# FlashPanelV6_2.net
KiCad netlist of a schematic drawn in EAGLE
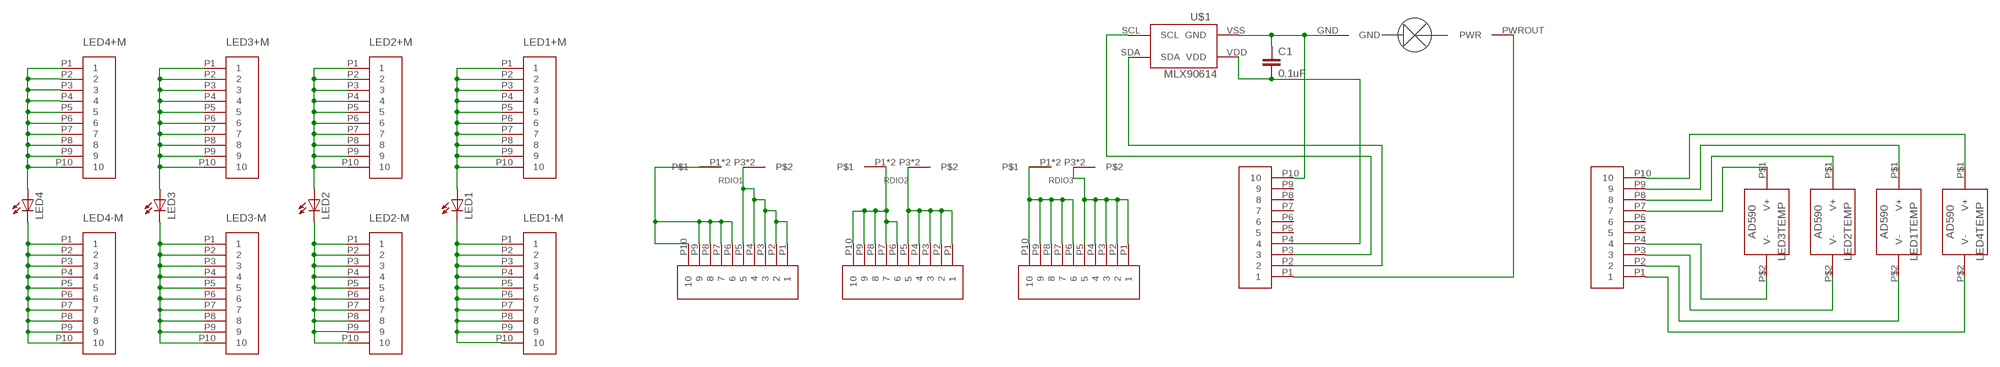
[diagram p0: schematic, sheet 1]

(export (version "E")
  (design (tool "Eeschema 10.0.6"))
  (components
    (comp (ref "ANTDEP1M")
      (value "10PINMALE")
      (footprint "eagle-import:10PINMALE")
      (libsource (lib "eagle-import") (part "cxm27_10PINMALE"))
    )
    (comp (ref "ANTDEP2M")
      (value "10PINMALE")
      (footprint "eagle-import:10PINMALE")
      (libsource (lib "eagle-import") (part "cxm27_10PINMALE"))
    )
    (comp (ref "ANTDEP3M")
      (value "10PINMALE")
      (footprint "eagle-import:10PINMALE")
      (libsource (lib "eagle-import") (part "cxm27_10PINMALE"))
    )
    (comp (ref "C1")
      (value "0.1uF")
      (footprint "eagle-import:0805")
      (libsource (lib "eagle-import") (part "CAP0805"))
    )
    (comp (ref "CONN13M")
      (value "10PINMALE")
      (footprint "eagle-import:10PINMALE")
      (libsource (lib "eagle-import") (part "cxm27_10PINMALE"))
    )
    (comp (ref "LED1")
      (value "CXM27")
      (footprint "eagle-import:CXM27")
      (libsource (lib "eagle-import") (part "CXM27"))
    )
    (comp (ref "LED1+M")
      (value "10PINMALE")
      (footprint "eagle-import:10PINMALE")
      (libsource (lib "eagle-import") (part "10PINMALE"))
    )
    (comp (ref "LED1-M")
      (value "10PINMALE")
      (footprint "eagle-import:10PINMALE")
      (libsource (lib "eagle-import") (part "10PINMALE"))
    )
    (comp (ref "LED1TEMP")
      (value "AD590-TH")
      (footprint "eagle-import:AD590TH")
      (libsource (lib "eagle-import") (part "AD590-TH"))
    )
    (comp (ref "LED2")
      (value "CXM27")
      (footprint "eagle-import:CXM27")
      (libsource (lib "eagle-import") (part "CXM27"))
    )
    (comp (ref "LED2+M")
      (value "10PINMALE")
      (footprint "eagle-import:10PINMALE")
      (libsource (lib "eagle-import") (part "10PINMALE"))
    )
    (comp (ref "LED2-M")
      (value "10PINMALE")
      (footprint "eagle-import:10PINMALE")
      (libsource (lib "eagle-import") (part "10PINMALE"))
    )
    (comp (ref "LED2TEMP")
      (value "AD590-TH")
      (footprint "eagle-import:AD590TH")
      (libsource (lib "eagle-import") (part "AD590-TH"))
    )
    (comp (ref "LED3")
      (value "CXM27")
      (footprint "eagle-import:CXM27")
      (libsource (lib "eagle-import") (part "CXM27"))
    )
    (comp (ref "LED3+M")
      (value "10PINMALE")
      (footprint "eagle-import:10PINMALE")
      (libsource (lib "eagle-import") (part "10PINMALE"))
    )
    (comp (ref "LED3-M")
      (value "10PINMALE")
      (footprint "eagle-import:10PINMALE")
      (libsource (lib "eagle-import") (part "10PINMALE"))
    )
    (comp (ref "LED3TEMP")
      (value "AD590-TH")
      (footprint "eagle-import:AD590TH")
      (libsource (lib "eagle-import") (part "AD590-TH"))
    )
    (comp (ref "LED4")
      (value "CXM27")
      (footprint "eagle-import:CXM27")
      (libsource (lib "eagle-import") (part "CXM27"))
    )
    (comp (ref "LED4+M")
      (value "10PINMALE")
      (footprint "eagle-import:10PINMALE")
      (libsource (lib "eagle-import") (part "10PINMALE"))
    )
    (comp (ref "LED4-M")
      (value "10PINMALE")
      (footprint "eagle-import:10PINMALE")
      (libsource (lib "eagle-import") (part "10PINMALE"))
    )
    (comp (ref "LED4TEMP")
      (value "AD590-TH")
      (footprint "eagle-import:AD590TH")
      (libsource (lib "eagle-import") (part "AD590-TH"))
    )
    (comp (ref "RDIO1")
      (value "RDIO")
      (footprint "eagle-import:RDIO_DPLY")
      (libsource (lib "eagle-import") (part "RDIO"))
    )
    (comp (ref "RDIO2")
      (value "RDIO")
      (footprint "eagle-import:RDIO_DPLY")
      (libsource (lib "eagle-import") (part "RDIO"))
    )
    (comp (ref "RDIO3")
      (value "RDIO")
      (footprint "eagle-import:RDIO_DPLY")
      (libsource (lib "eagle-import") (part "RDIO"))
    )
    (comp (ref "TEMPCONNM")
      (value "10PINMALE")
      (footprint "eagle-import:10PINMALE")
      (libsource (lib "eagle-import") (part "cxm27_10PINMALE"))
    )
    (comp (ref "U$1")
      (value "MXL90614")
      (footprint "eagle-import:MXL90620")
      (libsource (lib "eagle-import") (part "MXL90614"))
    )
    (comp (ref "U$2")
      (value "PHOTODETECTBOTTOM")
      (footprint "eagle-import:PHOTODETECTBOTTOM")
      (libsource (lib "eagle-import") (part "PHOTODETECTBOTTOM"))
    )
  )
  (nets
    (net (code "1") (name "Net-(ANTDEP1M-1)") (class "Default")
      (node (ref "ANTDEP1M") (pin "P1") (pinfunction "1_P1") (pintype "bidirectional"))
      (node (ref "ANTDEP1M") (pin "P2") (pinfunction "2_P2") (pintype "bidirectional"))
      (node (ref "ANTDEP1M") (pin "P3") (pinfunction "3_P3") (pintype "bidirectional"))
      (node (ref "ANTDEP1M") (pin "P4") (pinfunction "4_P4") (pintype "bidirectional"))
      (node (ref "ANTDEP1M") (pin "P5") (pinfunction "5_P5") (pintype "bidirectional"))
      (node (ref "RDIO1") (pin "P3") (pinfunction "P$2_P3") (pintype "bidirectional"))
      (node (ref "RDIO1") (pin "P4") (pinfunction "P$2_P4") (pintype "bidirectional"))
    )
    (net (code "2") (name "Net-(ANTDEP1M-10)") (class "Default")
      (node (ref "ANTDEP1M") (pin "P10") (pinfunction "10_P10") (pintype "bidirectional"))
      (node (ref "ANTDEP1M") (pin "P6") (pinfunction "6_P6") (pintype "bidirectional"))
      (node (ref "ANTDEP1M") (pin "P7") (pinfunction "7_P7") (pintype "bidirectional"))
      (node (ref "ANTDEP1M") (pin "P8") (pinfunction "8_P8") (pintype "bidirectional"))
      (node (ref "ANTDEP1M") (pin "P9") (pinfunction "9_P9") (pintype "bidirectional"))
      (node (ref "RDIO1") (pin "P1") (pinfunction "P$1_P1") (pintype "bidirectional"))
      (node (ref "RDIO1") (pin "P2") (pinfunction "P$1_P2") (pintype "bidirectional"))
    )
    (net (code "3") (name "Net-(ANTDEP2M-1)") (class "Default")
      (node (ref "ANTDEP2M") (pin "P1") (pinfunction "1_P1") (pintype "bidirectional"))
      (node (ref "ANTDEP2M") (pin "P2") (pinfunction "2_P2") (pintype "bidirectional"))
      (node (ref "ANTDEP2M") (pin "P3") (pinfunction "3_P3") (pintype "bidirectional"))
      (node (ref "ANTDEP2M") (pin "P4") (pinfunction "4_P4") (pintype "bidirectional"))
      (node (ref "ANTDEP2M") (pin "P5") (pinfunction "5_P5") (pintype "bidirectional"))
      (node (ref "RDIO2") (pin "P3") (pinfunction "P$2_P3") (pintype "bidirectional"))
      (node (ref "RDIO2") (pin "P4") (pinfunction "P$2_P4") (pintype "bidirectional"))
    )
    (net (code "4") (name "Net-(ANTDEP2M-10)") (class "Default")
      (node (ref "ANTDEP2M") (pin "P10") (pinfunction "10_P10") (pintype "bidirectional"))
      (node (ref "ANTDEP2M") (pin "P6") (pinfunction "6_P6") (pintype "bidirectional"))
      (node (ref "ANTDEP2M") (pin "P7") (pinfunction "7_P7") (pintype "bidirectional"))
      (node (ref "ANTDEP2M") (pin "P8") (pinfunction "8_P8") (pintype "bidirectional"))
      (node (ref "ANTDEP2M") (pin "P9") (pinfunction "9_P9") (pintype "bidirectional"))
      (node (ref "RDIO2") (pin "P1") (pinfunction "P$1_P1") (pintype "bidirectional"))
      (node (ref "RDIO2") (pin "P2") (pinfunction "P$1_P2") (pintype "bidirectional"))
    )
    (net (code "5") (name "Net-(ANTDEP3M-1)") (class "Default")
      (node (ref "ANTDEP3M") (pin "P1") (pinfunction "1_P1") (pintype "bidirectional"))
      (node (ref "ANTDEP3M") (pin "P2") (pinfunction "2_P2") (pintype "bidirectional"))
      (node (ref "ANTDEP3M") (pin "P3") (pinfunction "3_P3") (pintype "bidirectional"))
      (node (ref "ANTDEP3M") (pin "P4") (pinfunction "4_P4") (pintype "bidirectional"))
      (node (ref "ANTDEP3M") (pin "P5") (pinfunction "5_P5") (pintype "bidirectional"))
      (node (ref "RDIO3") (pin "P3") (pinfunction "P$2_P3") (pintype "bidirectional"))
      (node (ref "RDIO3") (pin "P4") (pinfunction "P$2_P4") (pintype "bidirectional"))
    )
    (net (code "6") (name "Net-(ANTDEP3M-10)") (class "Default")
      (node (ref "ANTDEP3M") (pin "P10") (pinfunction "10_P10") (pintype "bidirectional"))
      (node (ref "ANTDEP3M") (pin "P6") (pinfunction "6_P6") (pintype "bidirectional"))
      (node (ref "ANTDEP3M") (pin "P7") (pinfunction "7_P7") (pintype "bidirectional"))
      (node (ref "ANTDEP3M") (pin "P8") (pinfunction "8_P8") (pintype "bidirectional"))
      (node (ref "ANTDEP3M") (pin "P9") (pinfunction "9_P9") (pintype "bidirectional"))
      (node (ref "RDIO3") (pin "P1") (pinfunction "P$1_P1") (pintype "bidirectional"))
      (node (ref "RDIO3") (pin "P2") (pinfunction "P$1_P2") (pintype "bidirectional"))
    )
    (net (code "7") (name "Net-(CONN13M-1)") (class "Default")
      (node (ref "CONN13M") (pin "P1") (pinfunction "1_P1") (pintype "bidirectional"))
      (node (ref "U$2") (pin "PWROUT") (pinfunction "PWR_PWROUT") (pintype "bidirectional"))
    )
    (net (code "8") (name "Net-(CONN13M-2)") (class "Default")
      (node (ref "CONN13M") (pin "P2") (pinfunction "2_P2") (pintype "bidirectional"))
      (node (ref "U$1") (pin "SDA") (pinfunction "SDA_SDA") (pintype "bidirectional"))
    )
    (net (code "9") (name "Net-(CONN13M-3)") (class "Default")
      (node (ref "CONN13M") (pin "P3") (pinfunction "3_P3") (pintype "bidirectional"))
      (node (ref "U$1") (pin "SCL") (pinfunction "SCL_SCL") (pintype "bidirectional"))
    )
    (net (code "10") (name "Net-(CONN13M-4)") (class "Default")
      (node (ref "C1") (pin "2") (pinfunction "2_2") (pintype "passive"))
      (node (ref "CONN13M") (pin "P4") (pinfunction "4_P4") (pintype "bidirectional"))
      (node (ref "U$1") (pin "VDD") (pinfunction "VDD_VDD") (pintype "bidirectional"))
    )
    (net (code "11") (name "Net-(CONN13M-10)") (class "Default")
      (node (ref "C1") (pin "1") (pinfunction "1_1") (pintype "passive"))
      (node (ref "CONN13M") (pin "P10") (pinfunction "10_P10") (pintype "bidirectional"))
      (node (ref "U$1") (pin "VSS") (pinfunction "GND_VSS") (pintype "bidirectional"))
      (node (ref "U$2") (pin "GND") (pinfunction "GND_GND") (pintype "bidirectional"))
    )
    (net (code "12") (name "Net-(LED1+M-1)") (class "Default")
      (node (ref "LED1") (pin "ANODE") (pinfunction "A_ANODE") (pintype "passive"))
      (node (ref "LED1+M") (pin "P1") (pinfunction "1_P1") (pintype "bidirectional"))
      (node (ref "LED1+M") (pin "P10") (pinfunction "10_P10") (pintype "bidirectional"))
      (node (ref "LED1+M") (pin "P2") (pinfunction "2_P2") (pintype "bidirectional"))
      (node (ref "LED1+M") (pin "P3") (pinfunction "3_P3") (pintype "bidirectional"))
      (node (ref "LED1+M") (pin "P4") (pinfunction "4_P4") (pintype "bidirectional"))
      (node (ref "LED1+M") (pin "P5") (pinfunction "5_P5") (pintype "bidirectional"))
      (node (ref "LED1+M") (pin "P6") (pinfunction "6_P6") (pintype "bidirectional"))
      (node (ref "LED1+M") (pin "P7") (pinfunction "7_P7") (pintype "bidirectional"))
      (node (ref "LED1+M") (pin "P8") (pinfunction "8_P8") (pintype "bidirectional"))
      (node (ref "LED1+M") (pin "P9") (pinfunction "9_P9") (pintype "bidirectional"))
    )
    (net (code "13") (name "Net-(LED1-C)") (class "Default")
      (node (ref "LED1") (pin "CATHODE") (pinfunction "C_CATHODE") (pintype "passive"))
      (node (ref "LED1-M") (pin "P1") (pinfunction "1_P1") (pintype "bidirectional"))
      (node (ref "LED1-M") (pin "P10") (pinfunction "10_P10") (pintype "bidirectional"))
      (node (ref "LED1-M") (pin "P2") (pinfunction "2_P2") (pintype "bidirectional"))
      (node (ref "LED1-M") (pin "P3") (pinfunction "3_P3") (pintype "bidirectional"))
      (node (ref "LED1-M") (pin "P4") (pinfunction "4_P4") (pintype "bidirectional"))
      (node (ref "LED1-M") (pin "P5") (pinfunction "5_P5") (pintype "bidirectional"))
      (node (ref "LED1-M") (pin "P6") (pinfunction "6_P6") (pintype "bidirectional"))
      (node (ref "LED1-M") (pin "P7") (pinfunction "7_P7") (pintype "bidirectional"))
      (node (ref "LED1-M") (pin "P8") (pinfunction "8_P8") (pintype "bidirectional"))
      (node (ref "LED1-M") (pin "P9") (pinfunction "9_P9") (pintype "bidirectional"))
    )
    (net (code "14") (name "Net-(LED1TEMP-V+)") (class "Default")
      (node (ref "LED1TEMP") (pin "P$1") (pinfunction "V+_P$1") (pintype "bidirectional"))
      (node (ref "TEMPCONNM") (pin "P9") (pinfunction "9_P9") (pintype "bidirectional"))
    )
    (net (code "15") (name "Net-(LED1TEMP-V-)") (class "Default")
      (node (ref "LED1TEMP") (pin "P$2") (pinfunction "V-_P$2") (pintype "bidirectional"))
      (node (ref "TEMPCONNM") (pin "P2") (pinfunction "2_P2") (pintype "bidirectional"))
    )
    (net (code "16") (name "Net-(LED2+M-1)") (class "Default")
      (node (ref "LED2") (pin "ANODE") (pinfunction "A_ANODE") (pintype "passive"))
      (node (ref "LED2+M") (pin "P1") (pinfunction "1_P1") (pintype "bidirectional"))
      (node (ref "LED2+M") (pin "P10") (pinfunction "10_P10") (pintype "bidirectional"))
      (node (ref "LED2+M") (pin "P2") (pinfunction "2_P2") (pintype "bidirectional"))
      (node (ref "LED2+M") (pin "P3") (pinfunction "3_P3") (pintype "bidirectional"))
      (node (ref "LED2+M") (pin "P4") (pinfunction "4_P4") (pintype "bidirectional"))
      (node (ref "LED2+M") (pin "P5") (pinfunction "5_P5") (pintype "bidirectional"))
      (node (ref "LED2+M") (pin "P6") (pinfunction "6_P6") (pintype "bidirectional"))
      (node (ref "LED2+M") (pin "P7") (pinfunction "7_P7") (pintype "bidirectional"))
      (node (ref "LED2+M") (pin "P8") (pinfunction "8_P8") (pintype "bidirectional"))
      (node (ref "LED2+M") (pin "P9") (pinfunction "9_P9") (pintype "bidirectional"))
    )
    (net (code "17") (name "Net-(LED2-C)") (class "Default")
      (node (ref "LED2") (pin "CATHODE") (pinfunction "C_CATHODE") (pintype "passive"))
      (node (ref "LED2-M") (pin "P1") (pinfunction "1_P1") (pintype "bidirectional"))
      (node (ref "LED2-M") (pin "P10") (pinfunction "10_P10") (pintype "bidirectional"))
      (node (ref "LED2-M") (pin "P2") (pinfunction "2_P2") (pintype "bidirectional"))
      (node (ref "LED2-M") (pin "P3") (pinfunction "3_P3") (pintype "bidirectional"))
      (node (ref "LED2-M") (pin "P4") (pinfunction "4_P4") (pintype "bidirectional"))
      (node (ref "LED2-M") (pin "P5") (pinfunction "5_P5") (pintype "bidirectional"))
      (node (ref "LED2-M") (pin "P6") (pinfunction "6_P6") (pintype "bidirectional"))
      (node (ref "LED2-M") (pin "P7") (pinfunction "7_P7") (pintype "bidirectional"))
      (node (ref "LED2-M") (pin "P8") (pinfunction "8_P8") (pintype "bidirectional"))
      (node (ref "LED2-M") (pin "P9") (pinfunction "9_P9") (pintype "bidirectional"))
    )
    (net (code "18") (name "Net-(LED2TEMP-V+)") (class "Default")
      (node (ref "LED2TEMP") (pin "P$1") (pinfunction "V+_P$1") (pintype "bidirectional"))
      (node (ref "TEMPCONNM") (pin "P8") (pinfunction "8_P8") (pintype "bidirectional"))
    )
    (net (code "19") (name "Net-(LED2TEMP-V-)") (class "Default")
      (node (ref "LED2TEMP") (pin "P$2") (pinfunction "V-_P$2") (pintype "bidirectional"))
      (node (ref "TEMPCONNM") (pin "P3") (pinfunction "3_P3") (pintype "bidirectional"))
    )
    (net (code "20") (name "Net-(LED3+M-1)") (class "Default")
      (node (ref "LED3") (pin "ANODE") (pinfunction "A_ANODE") (pintype "passive"))
      (node (ref "LED3+M") (pin "P1") (pinfunction "1_P1") (pintype "bidirectional"))
      (node (ref "LED3+M") (pin "P10") (pinfunction "10_P10") (pintype "bidirectional"))
      (node (ref "LED3+M") (pin "P2") (pinfunction "2_P2") (pintype "bidirectional"))
      (node (ref "LED3+M") (pin "P3") (pinfunction "3_P3") (pintype "bidirectional"))
      (node (ref "LED3+M") (pin "P4") (pinfunction "4_P4") (pintype "bidirectional"))
      (node (ref "LED3+M") (pin "P5") (pinfunction "5_P5") (pintype "bidirectional"))
      (node (ref "LED3+M") (pin "P6") (pinfunction "6_P6") (pintype "bidirectional"))
      (node (ref "LED3+M") (pin "P7") (pinfunction "7_P7") (pintype "bidirectional"))
      (node (ref "LED3+M") (pin "P8") (pinfunction "8_P8") (pintype "bidirectional"))
      (node (ref "LED3+M") (pin "P9") (pinfunction "9_P9") (pintype "bidirectional"))
    )
    (net (code "21") (name "Net-(LED3-C)") (class "Default")
      (node (ref "LED3") (pin "CATHODE") (pinfunction "C_CATHODE") (pintype "passive"))
      (node (ref "LED3-M") (pin "P1") (pinfunction "1_P1") (pintype "bidirectional"))
      (node (ref "LED3-M") (pin "P10") (pinfunction "10_P10") (pintype "bidirectional"))
      (node (ref "LED3-M") (pin "P2") (pinfunction "2_P2") (pintype "bidirectional"))
      (node (ref "LED3-M") (pin "P3") (pinfunction "3_P3") (pintype "bidirectional"))
      (node (ref "LED3-M") (pin "P4") (pinfunction "4_P4") (pintype "bidirectional"))
      (node (ref "LED3-M") (pin "P5") (pinfunction "5_P5") (pintype "bidirectional"))
      (node (ref "LED3-M") (pin "P6") (pinfunction "6_P6") (pintype "bidirectional"))
      (node (ref "LED3-M") (pin "P7") (pinfunction "7_P7") (pintype "bidirectional"))
      (node (ref "LED3-M") (pin "P8") (pinfunction "8_P8") (pintype "bidirectional"))
      (node (ref "LED3-M") (pin "P9") (pinfunction "9_P9") (pintype "bidirectional"))
    )
    (net (code "22") (name "Net-(LED3TEMP-V+)") (class "Default")
      (node (ref "LED3TEMP") (pin "P$1") (pinfunction "V+_P$1") (pintype "bidirectional"))
      (node (ref "TEMPCONNM") (pin "P7") (pinfunction "7_P7") (pintype "bidirectional"))
    )
    (net (code "23") (name "Net-(LED3TEMP-V-)") (class "Default")
      (node (ref "LED3TEMP") (pin "P$2") (pinfunction "V-_P$2") (pintype "bidirectional"))
      (node (ref "TEMPCONNM") (pin "P4") (pinfunction "4_P4") (pintype "bidirectional"))
    )
    (net (code "24") (name "Net-(LED4+M-1)") (class "Default")
      (node (ref "LED4") (pin "ANODE") (pinfunction "A_ANODE") (pintype "passive"))
      (node (ref "LED4+M") (pin "P1") (pinfunction "1_P1") (pintype "bidirectional"))
      (node (ref "LED4+M") (pin "P10") (pinfunction "10_P10") (pintype "bidirectional"))
      (node (ref "LED4+M") (pin "P2") (pinfunction "2_P2") (pintype "bidirectional"))
      (node (ref "LED4+M") (pin "P3") (pinfunction "3_P3") (pintype "bidirectional"))
      (node (ref "LED4+M") (pin "P4") (pinfunction "4_P4") (pintype "bidirectional"))
      (node (ref "LED4+M") (pin "P5") (pinfunction "5_P5") (pintype "bidirectional"))
      (node (ref "LED4+M") (pin "P6") (pinfunction "6_P6") (pintype "bidirectional"))
      (node (ref "LED4+M") (pin "P7") (pinfunction "7_P7") (pintype "bidirectional"))
      (node (ref "LED4+M") (pin "P8") (pinfunction "8_P8") (pintype "bidirectional"))
      (node (ref "LED4+M") (pin "P9") (pinfunction "9_P9") (pintype "bidirectional"))
    )
    (net (code "25") (name "Net-(LED4-C)") (class "Default")
      (node (ref "LED4") (pin "CATHODE") (pinfunction "C_CATHODE") (pintype "passive"))
      (node (ref "LED4-M") (pin "P1") (pinfunction "1_P1") (pintype "bidirectional"))
      (node (ref "LED4-M") (pin "P10") (pinfunction "10_P10") (pintype "bidirectional"))
      (node (ref "LED4-M") (pin "P2") (pinfunction "2_P2") (pintype "bidirectional"))
      (node (ref "LED4-M") (pin "P3") (pinfunction "3_P3") (pintype "bidirectional"))
      (node (ref "LED4-M") (pin "P4") (pinfunction "4_P4") (pintype "bidirectional"))
      (node (ref "LED4-M") (pin "P5") (pinfunction "5_P5") (pintype "bidirectional"))
      (node (ref "LED4-M") (pin "P6") (pinfunction "6_P6") (pintype "bidirectional"))
      (node (ref "LED4-M") (pin "P7") (pinfunction "7_P7") (pintype "bidirectional"))
      (node (ref "LED4-M") (pin "P8") (pinfunction "8_P8") (pintype "bidirectional"))
      (node (ref "LED4-M") (pin "P9") (pinfunction "9_P9") (pintype "bidirectional"))
    )
    (net (code "26") (name "Net-(LED4TEMP-V+)") (class "Default")
      (node (ref "LED4TEMP") (pin "P$1") (pinfunction "V+_P$1") (pintype "bidirectional"))
      (node (ref "TEMPCONNM") (pin "P10") (pinfunction "10_P10") (pintype "bidirectional"))
    )
    (net (code "27") (name "Net-(LED4TEMP-V-)") (class "Default")
      (node (ref "LED4TEMP") (pin "P$2") (pinfunction "V-_P$2") (pintype "bidirectional"))
      (node (ref "TEMPCONNM") (pin "P1") (pinfunction "1_P1") (pintype "bidirectional"))
    )
    (net (code "28") (name "unconnected-(CONN13M-5-PadP5)") (class "Default")
      (node (ref "CONN13M") (pin "P5") (pinfunction "5_P5") (pintype "bidirectional"))
    )
    (net (code "29") (name "unconnected-(CONN13M-6-PadP6)") (class "Default")
      (node (ref "CONN13M") (pin "P6") (pinfunction "6_P6") (pintype "bidirectional"))
    )
    (net (code "30") (name "unconnected-(CONN13M-7-PadP7)") (class "Default")
      (node (ref "CONN13M") (pin "P7") (pinfunction "7_P7") (pintype "bidirectional"))
    )
    (net (code "31") (name "unconnected-(CONN13M-8-PadP8)") (class "Default")
      (node (ref "CONN13M") (pin "P8") (pinfunction "8_P8") (pintype "bidirectional"))
    )
    (net (code "32") (name "unconnected-(CONN13M-9-PadP9)") (class "Default")
      (node (ref "CONN13M") (pin "P9") (pinfunction "9_P9") (pintype "bidirectional"))
    )
    (net (code "33") (name "unconnected-(TEMPCONNM-5-PadP5)") (class "Default")
      (node (ref "TEMPCONNM") (pin "P5") (pinfunction "5_P5") (pintype "bidirectional"))
    )
    (net (code "34") (name "unconnected-(TEMPCONNM-6-PadP6)") (class "Default")
      (node (ref "TEMPCONNM") (pin "P6") (pinfunction "6_P6") (pintype "bidirectional"))
    )
  )
)
